# Booster_PA_OUT.net
KiCad netlist of a schematic drawn in Altium Designer
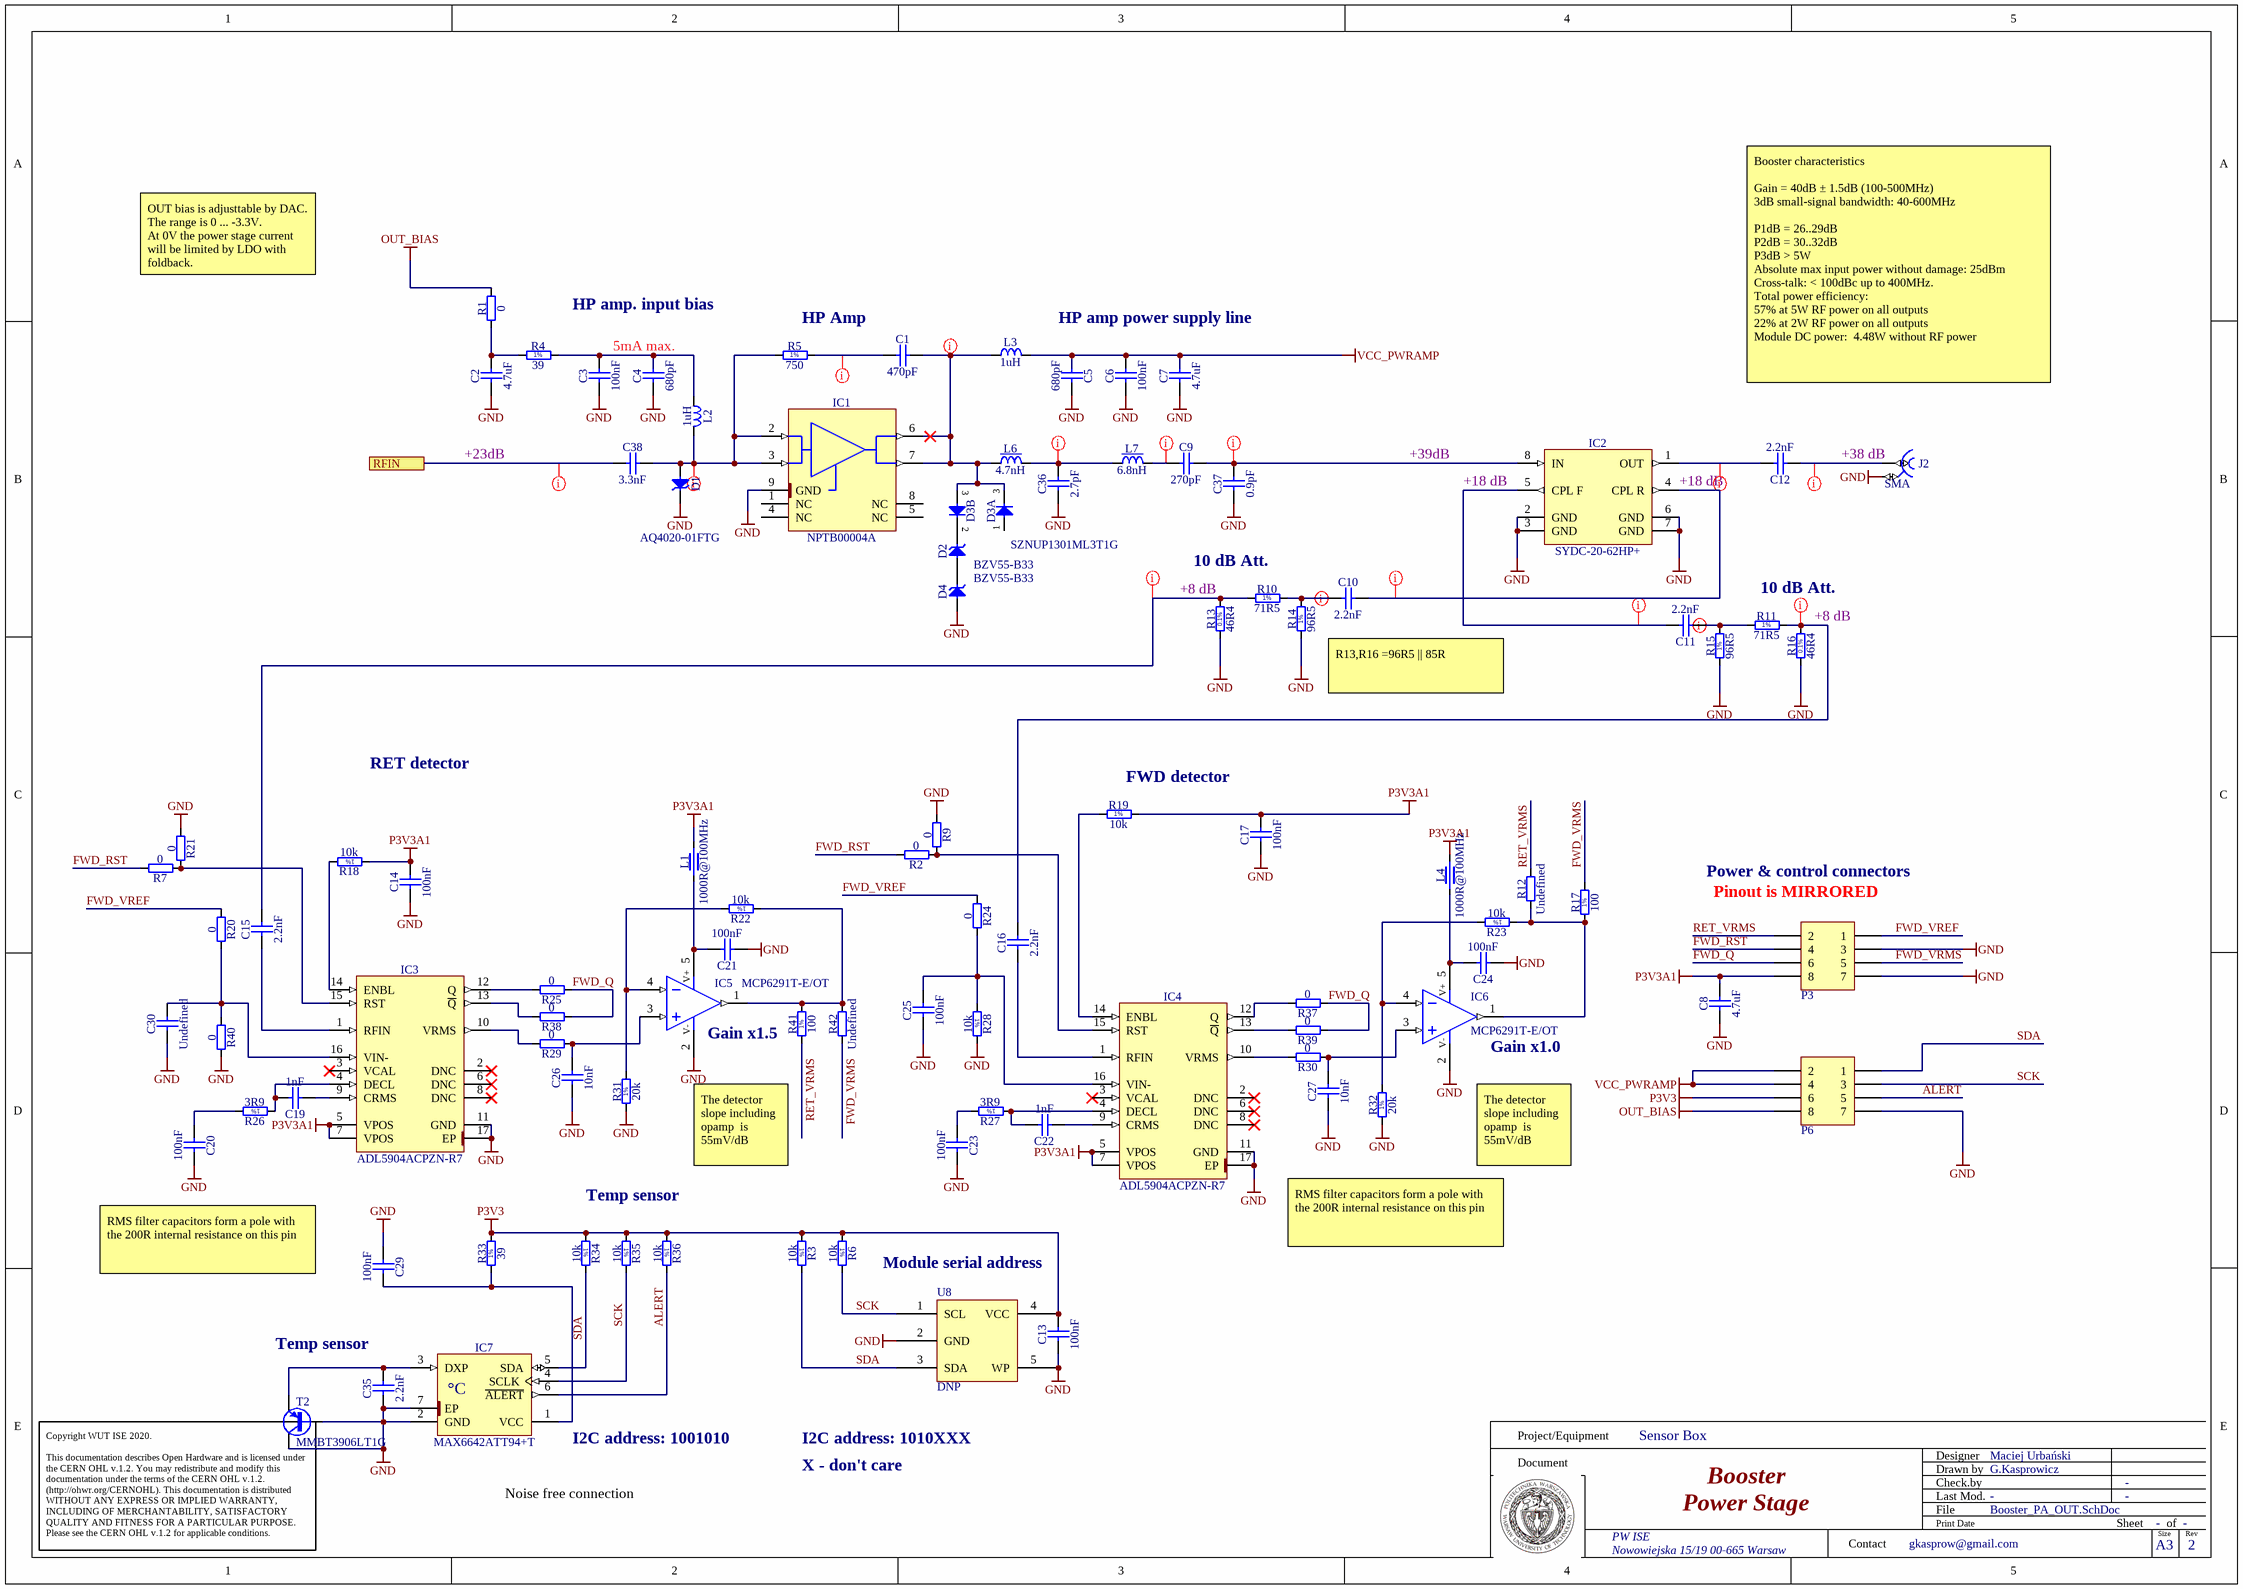
[diagram p0: Booster_PA_OUT.SchDoc]

(export (version "E")
  (design (tool "Eeschema 10.0.6"))
  (components
    (comp (ref "C1")
      (value "470pF")
      (footprint "CAPC1608X87N")
      (description "Non-polarised capacitor")
      (fields (field (name "PART NUMBER") "CC0603_470PF_50V_1%_NP0") (field (name "VOLTAGE") "50V"))
      (libsource (lib "Passives_RC") (part "CC0603_470PF_50V_1%_NP0"))
    )
    (comp (ref "C2")
      (value "4.7uF")
      (footprint "CAPC1709X95N")
      (description "Non-polarised capacitor")
      (fields
        (field (name "MANUFACTURER") "GENERIC")
        (field (name "MANUFACTURER PART NUMBER") "CC0603_4.7UF_16V_10%_X5R")
      )
      (libsource (lib "Capacitors") (part "Capacitor - non polarized"))
    )
    (comp (ref "C3")
      (value "100nF")
      (footprint "CAPC1005X55N")
      (description "Non-polarised capacitor")
      (fields
        (field (name "MANUFACTURER") "GENERIC")
        (field (name "MANUFACTURER PART NUMBER") "CC0402_100NF_50V_10%_X7R")
      )
      (libsource (lib "Capacitors") (part "Capacitor - non polarized"))
    )
    (comp (ref "C4")
      (value "680pF")
      (footprint "CAPC1608X87N")
      (description "Non-polarised capacitor")
      (fields
        (field (name "MANUFACTURER") "GENERIC")
        (field (name "MANUFACTURER PART NUMBER") "CC0603_680PF_50V_5%_NP0")
      )
      (libsource (lib "Capacitors") (part "Capacitor - non polarized"))
    )
    (comp (ref "C5")
      (value "680pF")
      (footprint "CAPC1608X87N")
      (description "Non-polarised capacitor")
      (fields
        (field (name "MANUFACTURER") "GENERIC")
        (field (name "MANUFACTURER PART NUMBER") "CC0603_680PF_50V_5%_NP0")
      )
      (libsource (lib "Capacitors") (part "Capacitor - non polarized"))
    )
    (comp (ref "C6")
      (value "100nF")
      (footprint "CAPC1005X55N")
      (description "Non-polarised capacitor")
      (fields
        (field (name "MANUFACTURER") "GENERIC")
        (field (name "MANUFACTURER PART NUMBER") "CC0402_100NF_50V_10%_X7R")
      )
      (libsource (lib "Capacitors") (part "Capacitor - non polarized"))
    )
    (comp (ref "C7")
      (value "4.7uF")
      (footprint "CAPC3225X270N")
      (description "Non-polarised capacitor")
      (fields (field (name "PART NUMBER") "CC1210_4.7UF_50V_10%_X7R") (field (name "VOLTAGE") "50V"))
      (libsource (lib "Capacitors") (part "Capacitor - non polarized"))
    )
    (comp (ref "C8")
      (value "4.7uF")
      (footprint "CAPC1709X95N")
      (description "Non-polarised capacitor")
      (fields
        (field (name "MANUFACTURER") "GENERIC")
        (field (name "MANUFACTURER PART NUMBER") "CC0603_4.7UF_16V_10%_X5R")
      )
      (libsource (lib "Capacitors") (part "Capacitor - non polarized"))
    )
    (comp (ref "C9")
      (value "270pF")
      (footprint "CAPC1608X87N")
      (description "Non-polarised capacitor")
      (fields (field (name "PART NUMBER") "CC0603_270PF_50V_1%_NP0") (field (name "VOLTAGE") "50V"))
      (libsource (lib "Passives_RC") (part "CC0603_270PF_50V_1%_NP0"))
    )
    (comp (ref "C10")
      (value "2.2nF")
      (footprint "CAPC1608X87N")
      (description "Non-polarised capacitor")
      (fields (field (name "PART NUMBER") "CC0603_2.2NF_50V_5%_C0G") (field (name "VOLTAGE") "50V"))
      (libsource (lib "Capacitors") (part "Capacitor - non polarized"))
    )
    (comp (ref "C11")
      (value "2.2nF")
      (footprint "CAPC1608X87N")
      (description "Non-polarised capacitor")
      (fields
        (field (name "MANUFACTURER") "GENERIC")
        (field (name "MANUFACTURER PART NUMBER") "CC0603_2.2NF_50V_5%_C0G")
      )
      (libsource (lib "Capacitors") (part "Capacitor - non polarized"))
    )
    (comp (ref "C12")
      (value "2.2nF")
      (footprint "CAPC1608X87N")
      (description "Non-polarised capacitor")
      (fields
        (field (name "MANUFACTURER") "GENERIC")
        (field (name "MANUFACTURER PART NUMBER") "CC0603_2.2NF_50V_5%_C0G")
      )
      (libsource (lib "Capacitors") (part "Capacitor - non polarized"))
    )
    (comp (ref "C13")
      (value "100nF")
      (footprint "CAPC1005X55N")
      (description "Non-polarised capacitor")
      (fields
        (field (name "MANUFACTURER") "GENERIC")
        (field (name "MANUFACTURER PART NUMBER") "CC0402_100NF_50V_10%_X7R")
      )
      (libsource (lib "Capacitors") (part "Capacitor - non polarized"))
    )
    (comp (ref "C14")
      (value "100nF")
      (footprint "CAPC1005X55N")
      (description "Non-polarised capacitor")
      (fields
        (field (name "MANUFACTURER") "GENERIC")
        (field (name "MANUFACTURER PART NUMBER") "CC0402_100NF_50V_10%_X7R")
      )
      (libsource (lib "Capacitors") (part "Capacitor - non polarized"))
    )
    (comp (ref "C15")
      (value "2.2nF")
      (footprint "CAPC1608X87N")
      (description "Non-polarised capacitor")
      (fields
        (field (name "MANUFACTURER") "GENERIC")
        (field (name "MANUFACTURER PART NUMBER") "CC0603_2.2NF_50V_5%_C0G")
      )
      (libsource (lib "Capacitors") (part "Capacitor - non polarized"))
    )
    (comp (ref "C16")
      (value "2.2nF")
      (footprint "CAPC1608X87N")
      (description "Non-polarised capacitor")
      (fields
        (field (name "MANUFACTURER") "GENERIC")
        (field (name "MANUFACTURER PART NUMBER") "CC0603_2.2NF_50V_5%_C0G")
      )
      (libsource (lib "Capacitors") (part "Capacitor - non polarized"))
    )
    (comp (ref "C17")
      (value "100nF")
      (footprint "CAPC1005X55N")
      (description "Non-polarised capacitor")
      (fields
        (field (name "MANUFACTURER") "GENERIC")
        (field (name "MANUFACTURER PART NUMBER") "CC0402_100NF_50V_10%_X7R")
      )
      (libsource (lib "Capacitors") (part "Capacitor - non polarized"))
    )
    (comp (ref "C19")
      (value "1nF")
      (footprint "CAPC1005X55N")
      (description "Non-polarised capacitor")
      (fields (field (name "PART NUMBER") "CC0402_1NF_50V_10%_X7R") (field (name "VOLTAGE") "50V"))
      (libsource (lib "Capacitors") (part "Capacitor - non polarized"))
    )
    (comp (ref "C20")
      (value "100nF")
      (footprint "CAPC1005X55N")
      (description "Non-polarised capacitor")
      (fields
        (field (name "MANUFACTURER") "GENERIC")
        (field (name "MANUFACTURER PART NUMBER") "CC0402_100NF_50V_10%_X7R")
      )
      (libsource (lib "Capacitors") (part "Capacitor - non polarized"))
    )
    (comp (ref "C21")
      (value "100nF")
      (footprint "CAPC1005X55N")
      (description "Non-polarised capacitor")
      (fields
        (field (name "MANUFACTURER") "GENERIC")
        (field (name "MANUFACTURER PART NUMBER") "CC0402_100NF_50V_10%_X7R")
      )
      (libsource (lib "Capacitors") (part "Capacitor - non polarized"))
    )
    (comp (ref "C22")
      (value "1nF")
      (footprint "CAPC1005X55N")
      (description "Non-polarised capacitor")
      (fields (field (name "PART NUMBER") "CC0402_1NF_50V_10%_X7R") (field (name "VOLTAGE") "50V"))
      (libsource (lib "Capacitors") (part "Capacitor - non polarized"))
    )
    (comp (ref "C23")
      (value "100nF")
      (footprint "CAPC1005X55N")
      (description "Non-polarised capacitor")
      (fields
        (field (name "MANUFACTURER") "GENERIC")
        (field (name "MANUFACTURER PART NUMBER") "CC0402_100NF_50V_10%_X7R")
      )
      (libsource (lib "Capacitors") (part "Capacitor - non polarized"))
    )
    (comp (ref "C24")
      (value "100nF")
      (footprint "CAPC1005X55N")
      (description "Non-polarised capacitor")
      (fields
        (field (name "MANUFACTURER") "GENERIC")
        (field (name "MANUFACTURER PART NUMBER") "CC0402_100NF_50V_10%_X7R")
      )
      (libsource (lib "Capacitors") (part "Capacitor - non polarized"))
    )
    (comp (ref "C25")
      (value "100nF")
      (footprint "CAPC1005X55N")
      (description "Non-polarised capacitor")
      (fields
        (field (name "MANUFACTURER") "GENERIC")
        (field (name "MANUFACTURER PART NUMBER") "CC0402_100NF_50V_10%_X7R")
      )
      (libsource (lib "Capacitors") (part "Capacitor - non polarized"))
    )
    (comp (ref "C26")
      (value "10nF")
      (footprint "CAPC1005X55N")
      (description "Non-polarised capacitor")
      (fields
        (field (name "MANUFACTURER") "GENERIC")
        (field (name "MANUFACTURER PART NUMBER") "CC0402_10NF_25V_10%_X7R")
      )
      (libsource (lib "Capacitors") (part "Capacitor - non polarized"))
    )
    (comp (ref "C27")
      (value "10nF")
      (footprint "CAPC1005X55N")
      (description "Non-polarised capacitor")
      (fields
        (field (name "MANUFACTURER") "GENERIC")
        (field (name "MANUFACTURER PART NUMBER") "CC0402_10NF_25V_10%_X7R")
      )
      (libsource (lib "Capacitors") (part "Capacitor - non polarized"))
    )
    (comp (ref "C29")
      (value "100nF")
      (footprint "CAPC1005X55N")
      (description "Non-polarised capacitor")
      (fields
        (field (name "MANUFACTURER") "GENERIC")
        (field (name "MANUFACTURER PART NUMBER") "CC0402_100NF_50V_10%_X7R")
      )
      (libsource (lib "Capacitors") (part "Capacitor - non polarized"))
    )
    (comp (ref "C30")
      (value "Undefined")
      (footprint "CAPC1608X90N")
      (description "Non-polarised capacitor")
      (fields (field (name "PART NUMBER") "CC0603_NO-VALUE"))
      (libsource (lib "Capacitors") (part "Capacitor - non polarized"))
    )
    (comp (ref "C35")
      (value "2.2nF")
      (footprint "CAPC1608X87N")
      (description "Non-polarised capacitor")
      (fields
        (field (name "MANUFACTURER") "GENERIC")
        (field (name "MANUFACTURER PART NUMBER") "CC0603_2.2NF_50V_5%_C0G")
      )
      (libsource (lib "Capacitors") (part "Capacitor - non polarized"))
    )
    (comp (ref "C36")
      (value "2.7pF")
      (footprint "CAPC1608X87N")
      (description "Non-polarised capacitor")
      (fields (field (name "PART NUMBER") "CC0603_2.7PF_50V_0.25PF_NP0") (field (name "VOLTAGE") "50V"))
      (libsource (lib "Capacitors") (part "Capacitor - non polarized"))
    )
    (comp (ref "C37")
      (value "0.9pF")
      (footprint "CAPC1608X87N")
      (description "Non-polarised capacitor")
      (fields (field (name "PART NUMBER") "CC0603_0.9PF_50V_0.05PF_NP0") (field (name "VOLTAGE") "50V"))
      (libsource (lib "Passives_RC") (part "CC0603_0.9PF_50V_0.05PF_NP0"))
    )
    (comp (ref "C38")
      (value "3.3nF")
      (footprint "CAPC1608X87N")
      (description "Non-polarised capacitor")
      (fields
        (field (name "MANUFACTURER") "GENERIC")
        (field (name "MANUFACTURER PART NUMBER") "CC0603_3.3NF_50V_5%_C0G")
      )
      (libsource (lib "Capacitors") (part "Capacitor - non polarized"))
    )
    (comp (ref "D1")
      (value "AQ4020-01FTG")
      (footprint "SOD2512X110N")
      (description "4V Transient Voltage Suppressor Diode (Uni-Directional)")
      (fields (field (name "VOLTAGE") "4V") (field (name "POWER") "735W"))
      (libsource (lib "Diodes") (part "D_TVS_AQ4020-01FTG"))
    )
    (comp (ref "D2")
      (value "BZV55-B33")
      (footprint "DIOMELF3515N")
      (description "Zener Diode")
      (fields (field (name "VOLTAGE") "33V") (field (name "POWER") "500mW"))
      (libsource (lib "ICs And Semiconductors") (part "Diode Zener"))
    )
    (comp (ref "D3")
      (value "SZNUP1301ML3T1G")
      (footprint "SOT95P240X110-3N")
      (description "Low Capacitance Diode Array for ESD Protection in a Single Data Line")
      (fields (field (name "VOLTAGE") "70V") (field (name "POWER") "215mA"))
      (libsource (lib "Diodes") (part "D_TVS_SZNUP1301ML3T1G"))
    )
    (comp (ref "D4")
      (value "BZV55-B33")
      (footprint "DIOMELF3515N")
      (description "Zener Diode")
      (fields (field (name "VOLTAGE") "33V") (field (name "POWER") "500mW"))
      (libsource (lib "ICs And Semiconductors") (part "Diode Zener"))
    )
    (comp (ref "IC1")
      (value "NPTB00004A")
      (footprint "SOIC127P610X167-9N-R245X335")
      (description "GaN Wideband Transistor 28V, 5W, DC - 6GHz")
      (fields (field (name "MANUFACTURER") "MACOM"))
      (libsource (lib "ICs And Semiconductors") (part "NPTB00004A"))
    )
    (comp (ref "IC2")
      (value "SYDC-20-62HP+")
      (footprint "MINI-CIRCUITS_AH202-1")
      (description "50Ohm, 10 to 540MHz, 25W, 20dB Bi-Directional Coupler")
      (fields (field (name "MANUFACTURER") "MINI-CIRCUITS"))
      (libsource (lib "ICs And Semiconductors") (part "SYDC-20-62HP+"))
    )
    (comp (ref "IC3")
      (value "ADL5904ACPZN-R7")
      (footprint "QFN50P300X300X80-17N-S175")
      (description "DC to 6 GHz, 45 dB TruPwr Detector With Envelope Threshold Detection")
      (fields (field (name "MANUFACTURER") "ANALOG DEVICES"))
      (libsource (lib "ICs And Semiconductors") (part "ADL5904"))
    )
    (comp (ref "IC4")
      (value "ADL5904ACPZN-R7")
      (footprint "QFN50P300X300X80-17N-S175")
      (description "DC to 6 GHz, 45 dB TruPwr Detector With Envelope Threshold Detection")
      (fields (field (name "MANUFACTURER") "ANALOG DEVICES"))
      (libsource (lib "ICs And Semiconductors") (part "ADL5904"))
    )
    (comp (ref "IC5")
      (value "MCP6291T-E/OT")
      (footprint "SOT95P270X145-5N")
      (description "Operational Amplifier")
      (fields (field (name "MANUFACTURER") "MICROCHIP TECHNOLOGY"))
      (libsource (lib "ICs And Semiconductors") (part "Operational Amplifier Type7"))
    )
    (comp (ref "IC6")
      (value "MCP6291T-E/OT")
      (footprint "SOT95P270X145-5N")
      (description "Operational Amplifier")
      (fields (field (name "MANUFACTURER") "MICROCHIP TECHNOLOGY"))
      (libsource (lib "ICs And Semiconductors") (part "Operational Amplifier Type7"))
    )
    (comp (ref "IC7")
      (value "MAX6642ATT94+T")
      (footprint "SON95P300X300X80-7N-R160X240")
      (description "±1°C, SMBus-Compatible Remote/Local Temperature Sensor with Overtemperature Alarm")
      (fields (field (name "MANUFACTURER") "MAXIM"))
      (libsource (lib "ICs And Semiconductors") (part "MAX6642ATT"))
    )
    (comp (ref "J2")
      (value "SMA")
      (footprint "MOLEX_73251-2120")
      (description "50 Ohm, SMA Edge Mount PCB, With Jam Nut And Lock Washer")
      (fields (field (name "PART NUMBER") "MOLEX_73251-2120") (field (name "MANUFACTURER") "MOLEX"))
      (libsource (lib "Connectors") (part "CON_SMA_RA_SMD_73251-2120"))
    )
    (comp (ref "L1")
      (value "1000R@100MHz")
      (footprint "INDC1608X95N")
      (fields
        (field (name "MANUFACTURER") "MURATA")
        (field (name "MANUFACTURER PART NUMBER") "BLM18HE102SN1")
        (field (name "PART NUMBER") "IND0603_MURATA_BLM18HE102SN1")
      )
      (libsource (lib "Inductors & Transformers") (part "Ferrite Bead"))
    )
    (comp (ref "L2")
      (value "1uH")
      (footprint "INDC2113X60N")
      (description "Inductor")
      (fields (field (name "PART NUMBER") "IND0805_1UH_20%_WURTH_74479773210") (field (name "POWER") "800mA"))
      (libsource (lib "Inductors & Transformers") (part "Inductor"))
    )
    (comp (ref "L3")
      (value "1uH")
      (footprint "INDC2113X60N")
      (description "Inductor")
      (fields (field (name "PART NUMBER") "IND0805_1UH_20%_WURTH_74479773210") (field (name "POWER") "800mA"))
      (libsource (lib "") (part "Inductor_1"))
    )
    (comp (ref "L4")
      (value "1000R@100MHz")
      (footprint "INDC1608X95N")
      (fields
        (field (name "MANUFACTURER") "MURATA")
        (field (name "MANUFACTURER PART NUMBER") "BLM18HE102SN1")
        (field (name "PART NUMBER") "IND0603_MURATA_BLM18HE102SN1")
      )
      (libsource (lib "Inductors & Transformers") (part "Ferrite Bead"))
    )
    (comp (ref "L6")
      (value "4.7nH")
      (footprint "IND_MURATA_LQW18AN_G8")
      (description "Inductor With Core")
      (fields
        (field (name "PART NUMBER") "IND0603_4.7NH_2%_MURATA_LQW18AN4N7G8Z")
        (field (name "POWER") "1.5A")
      )
      (libsource (lib "Inductors & Transformers") (part "Inductor With Magnetic core"))
    )
    (comp (ref "L7")
      (value "6.8nH")
      (footprint "IND_MURATA_LQW18AN_G8")
      (description "Inductor With Core")
      (fields
        (field (name "PART NUMBER") "IND0603_6.8NH_2%_MURATA_LQW18AN6N8G8Z")
        (field (name "POWER") "1.9A")
      )
      (libsource (lib "Inductors & Transformers") (part "Inductor With Magnetic core"))
    )
    (comp (ref "P3")
      (value "ZL264-8DG")
      (footprint "HDR2X4_SMD")
      (description "Header, 4-Pin, Dual Row")
      (libsource (lib "onyks") (part "HDR2X4"))
    )
    (comp (ref "P6")
      (value "ZL264-8DG")
      (footprint "HDR2X4_SMD")
      (description "Header, 4-Pin, Dual Row")
      (libsource (lib "onyks") (part "HDR2X4"))
    )
    (comp (ref "R1")
      (value "0")
      (footprint "RESC1005X40N")
      (description "Resistor")
      (fields
        (field (name "MANUFACTURER") "GENERIC")
        (field (name "MANUFACTURER PART NUMBER") "R0402_0R_JUMPER")
      )
      (libsource (lib "Resistors") (part "Resistor"))
    )
    (comp (ref "R2")
      (value "0")
      (footprint "RESC1005X40N")
      (description "Resistor")
      (fields
        (field (name "MANUFACTURER") "GENERIC")
        (field (name "MANUFACTURER PART NUMBER") "R0402_0R_JUMPER")
      )
      (libsource (lib "Resistors") (part "Resistor"))
    )
    (comp (ref "R3")
      (value "10k")
      (footprint "RESC1005X40N")
      (description "Resistor - 1%")
      (fields
        (field (name "MANUFACTURER") "GENERIC")
        (field (name "MANUFACTURER PART NUMBER") "R0402_10K_1%_0.0625W_100PPM")
      )
      (libsource (lib "Resistors") (part "Resistor - 1%"))
    )
    (comp (ref "R4")
      (value "39")
      (footprint "RESC1608X55N")
      (description "Resistor - 1%")
      (fields (field (name "PART NUMBER") "R0603_39R_1%_0.1W_100PPM") (field (name "POWER") "0.1W"))
      (libsource (lib "Resistors") (part "Resistor - 1%"))
    )
    (comp (ref "R5")
      (value "750")
      (footprint "RESC1608X55N")
      (description "Resistor - 1%")
      (fields (field (name "PART NUMBER") "R0603_750R_1%_0.1W_100PPM") (field (name "POWER") "0.1W"))
      (libsource (lib "Resistors") (part "Resistor - 1%"))
    )
    (comp (ref "R6")
      (value "10k")
      (footprint "RESC1005X40N")
      (description "Resistor - 1%")
      (fields
        (field (name "MANUFACTURER") "GENERIC")
        (field (name "MANUFACTURER PART NUMBER") "R0402_10K_1%_0.0625W_100PPM")
      )
      (libsource (lib "Resistors") (part "Resistor - 1%"))
    )
    (comp (ref "R7")
      (value "0")
      (footprint "RESC1005X40N")
      (description "Resistor")
      (fields
        (field (name "MANUFACTURER") "GENERIC")
        (field (name "MANUFACTURER PART NUMBER") "R0402_0R_JUMPER")
      )
      (libsource (lib "Resistors") (part "Resistor"))
    )
    (comp (ref "R9")
      (value "0")
      (footprint "RESC1005X40N")
      (description "Resistor")
      (fields
        (field (name "MANUFACTURER") "GENERIC")
        (field (name "MANUFACTURER PART NUMBER") "R0402_0R_JUMPER")
      )
      (libsource (lib "Resistors") (part "Resistor"))
    )
    (comp (ref "R10")
      (value "71R5")
      (footprint "RESC1608X55N")
      (description "Resistor - 1%")
      (fields (field (name "PART NUMBER") "R0603_71R5_1%_0.1W_100PPM") (field (name "POWER") "0.1W"))
      (libsource (lib "Resistors") (part "Resistor - 1%"))
    )
    (comp (ref "R11")
      (value "71R5")
      (footprint "RESC1608X55N")
      (description "Resistor - 1%")
      (fields (field (name "PART NUMBER") "R0603_71R5_1%_0.1W_100PPM") (field (name "POWER") "0.1W"))
      (libsource (lib "Resistors") (part "Resistor - 1%"))
    )
    (comp (ref "R12")
      (value "Undefined")
      (footprint "RESC1608X55N")
      (description "Resistor")
      (fields (field (name "MANUFACTURER PART NUMBER") "R0603_NO-VALUE"))
      (libsource (lib "Resistors") (part "Resistor"))
    )
    (comp (ref "R13")
      (value "46R4")
      (footprint "RESC1608X55N")
      (description "Resistor - 0.1%")
      (fields (field (name "PART NUMBER") "R0603_46R4_0.1%_0.063W_10PPM") (field (name "POWER") "0.063W"))
      (libsource (lib "Resistors") (part "Resistor - 0.1%"))
    )
    (comp (ref "R14")
      (value "96R5")
      (footprint "RESC1608X55N")
      (description "Resistor - 0.5%")
      (fields (field (name "PART NUMBER") "R0603_96R5_0.5%_0.1W_50PPM") (field (name "POWER") "0.1W"))
      (libsource (lib "Passives_RC") (part "R0603_96R5_0.5%_0.1W_50PPM"))
    )
    (comp (ref "R15")
      (value "96R5")
      (footprint "RESC1608X55N")
      (description "Resistor - 0.5%")
      (fields (field (name "PART NUMBER") "R0603_96R5_0.5%_0.1W_50PPM") (field (name "POWER") "0.1W"))
      (libsource (lib "Passives_RC") (part "R0603_96R5_0.5%_0.1W_50PPM"))
    )
    (comp (ref "R16")
      (value "46R4")
      (footprint "RESC1608X55N")
      (description "Resistor - 0.1%")
      (fields (field (name "PART NUMBER") "R0603_46R4_0.1%_0.063W_10PPM") (field (name "POWER") "0.063W"))
      (libsource (lib "Resistors") (part "Resistor - 0.1%"))
    )
    (comp (ref "R17")
      (value "100")
      (footprint "RESC1608X55N")
      (description "Resistor - 1%")
      (fields
        (field (name "MANUFACTURER") "GENERIC")
        (field (name "MANUFACTURER PART NUMBER") "R0603_100R_1%_0.1W_100PPM")
      )
      (libsource (lib "Resistors") (part "Resistor - 1%"))
    )
    (comp (ref "R18")
      (value "10k")
      (footprint "RESC1005X40N")
      (description "Resistor - 1%")
      (fields
        (field (name "MANUFACTURER") "GENERIC")
        (field (name "MANUFACTURER PART NUMBER") "R0402_10K_1%_0.0625W_100PPM")
      )
      (libsource (lib "Resistors") (part "Resistor - 1%"))
    )
    (comp (ref "R19")
      (value "10k")
      (footprint "RESC1005X40N")
      (description "Resistor - 1%")
      (fields (field (name "PART NUMBER") "R0402_10K_1%_0.0625W_100PPM") (field (name "POWER") "0.0625W"))
      (libsource (lib "Resistors") (part "Resistor - 1%"))
    )
    (comp (ref "R20")
      (value "0")
      (footprint "RESC1005X40N")
      (description "Resistor")
      (fields
        (field (name "MANUFACTURER") "GENERIC")
        (field (name "MANUFACTURER PART NUMBER") "R0402_0R_JUMPER")
      )
      (libsource (lib "Resistors") (part "Resistor"))
    )
    (comp (ref "R21")
      (value "0")
      (footprint "RESC1005X40N")
      (description "Resistor")
      (fields
        (field (name "MANUFACTURER") "GENERIC")
        (field (name "MANUFACTURER PART NUMBER") "R0402_0R_JUMPER")
      )
      (libsource (lib "Resistors") (part "Resistor"))
    )
    (comp (ref "R22")
      (value "10k")
      (footprint "RESC1005X40N")
      (description "Resistor - 1%")
      (fields
        (field (name "MANUFACTURER") "GENERIC")
        (field (name "MANUFACTURER PART NUMBER") "R0402_10K_1%_0.0625W_100PPM")
      )
      (libsource (lib "Resistors") (part "Resistor - 1%"))
    )
    (comp (ref "R23")
      (value "10k")
      (footprint "RESC1005X40N")
      (description "Resistor - 1%")
      (fields
        (field (name "MANUFACTURER") "GENERIC")
        (field (name "MANUFACTURER PART NUMBER") "R0402_10K_1%_0.0625W_100PPM")
      )
      (libsource (lib "Resistors") (part "Resistor - 1%"))
    )
    (comp (ref "R24")
      (value "0")
      (footprint "RESC1005X40N")
      (description "Resistor")
      (fields
        (field (name "MANUFACTURER") "GENERIC")
        (field (name "MANUFACTURER PART NUMBER") "R0402_0R_JUMPER")
      )
      (libsource (lib "Resistors") (part "Resistor"))
    )
    (comp (ref "R25")
      (value "0")
      (footprint "RESC1005X40N")
      (description "Resistor")
      (fields
        (field (name "MANUFACTURER") "GENERIC")
        (field (name "MANUFACTURER PART NUMBER") "R0402_0R_JUMPER")
      )
      (libsource (lib "Resistors") (part "Resistor"))
    )
    (comp (ref "R26")
      (value "3R9")
      (footprint "RESC1005X40N")
      (description "Resistor - 1%")
      (fields (field (name "PART NUMBER") "R0402_3R9_1%_0.0625W_200PPM") (field (name "POWER") "0.0625W"))
      (libsource (lib "Resistors") (part "Resistor - 1%"))
    )
    (comp (ref "R27")
      (value "3R9")
      (footprint "RESC1005X40N")
      (description "Resistor - 1%")
      (fields (field (name "PART NUMBER") "R0402_3R9_1%_0.0625W_200PPM") (field (name "POWER") "0.0625W"))
      (libsource (lib "Resistors") (part "Resistor - 1%"))
    )
    (comp (ref "R28")
      (value "10k")
      (footprint "RESC1005X40N")
      (description "Resistor - 1%")
      (fields
        (field (name "MANUFACTURER") "GENERIC")
        (field (name "MANUFACTURER PART NUMBER") "R0402_10K_1%_0.0625W_100PPM")
      )
      (libsource (lib "Resistors") (part "Resistor - 1%"))
    )
    (comp (ref "R29")
      (value "0")
      (footprint "RESC1005X40N")
      (description "Resistor")
      (fields
        (field (name "MANUFACTURER") "GENERIC")
        (field (name "MANUFACTURER PART NUMBER") "R0402_0R_JUMPER")
      )
      (libsource (lib "Resistors") (part "Resistor"))
    )
    (comp (ref "R30")
      (value "0")
      (footprint "RESC1005X40N")
      (description "Resistor")
      (fields
        (field (name "MANUFACTURER") "GENERIC")
        (field (name "MANUFACTURER PART NUMBER") "R0402_0R_JUMPER")
      )
      (libsource (lib "Resistors") (part "Resistor"))
    )
    (comp (ref "R31")
      (value "20k")
      (footprint "RESC1608X55N")
      (description "Resistor - 1%")
      (fields (field (name "PART NUMBER") "R0603_20K_1%_0.1W_100PPM") (field (name "POWER") "0.1W"))
      (libsource (lib "Resistors") (part "Resistor - 1%"))
    )
    (comp (ref "R32")
      (value "20k")
      (footprint "RESC1608X55N")
      (description "Resistor - 1%")
      (fields (field (name "PART NUMBER") "R0603_20K_1%_0.1W_100PPM") (field (name "POWER") "0.1W"))
      (libsource (lib "Resistors") (part "Resistor - 1%"))
    )
    (comp (ref "R33")
      (value "39")
      (footprint "RESC1608X55N")
      (description "Resistor - 1%")
      (fields (field (name "PART NUMBER") "R0603_39R_1%_0.1W_100PPM") (field (name "POWER") "0.1W"))
      (libsource (lib "Resistors") (part "Resistor - 1%"))
    )
    (comp (ref "R34")
      (value "10k")
      (footprint "RESC1005X40N")
      (description "Resistor - 1%")
      (fields
        (field (name "MANUFACTURER") "GENERIC")
        (field (name "MANUFACTURER PART NUMBER") "R0402_10K_1%_0.0625W_100PPM")
      )
      (libsource (lib "Resistors") (part "Resistor - 1%"))
    )
    (comp (ref "R35")
      (value "10k")
      (footprint "RESC1005X40N")
      (description "Resistor - 1%")
      (fields
        (field (name "MANUFACTURER") "GENERIC")
        (field (name "MANUFACTURER PART NUMBER") "R0402_10K_1%_0.0625W_100PPM")
      )
      (libsource (lib "Resistors") (part "Resistor - 1%"))
    )
    (comp (ref "R36")
      (value "10k")
      (footprint "RESC1005X40N")
      (description "Resistor - 1%")
      (fields
        (field (name "MANUFACTURER") "GENERIC")
        (field (name "MANUFACTURER PART NUMBER") "R0402_10K_1%_0.0625W_100PPM")
      )
      (libsource (lib "Resistors") (part "Resistor - 1%"))
    )
    (comp (ref "R37")
      (value "0")
      (footprint "RESC1005X40N")
      (description "Resistor")
      (fields
        (field (name "MANUFACTURER") "GENERIC")
        (field (name "MANUFACTURER PART NUMBER") "R0402_0R_JUMPER")
      )
      (libsource (lib "Resistors") (part "Resistor"))
    )
    (comp (ref "R38")
      (value "0")
      (footprint "RESC1005X40N")
      (description "Resistor")
      (fields
        (field (name "MANUFACTURER") "GENERIC")
        (field (name "MANUFACTURER PART NUMBER") "R0402_0R_JUMPER")
      )
      (libsource (lib "Resistors") (part "Resistor"))
    )
    (comp (ref "R39")
      (value "0")
      (footprint "RESC1005X40N")
      (description "Resistor")
      (fields
        (field (name "MANUFACTURER") "GENERIC")
        (field (name "MANUFACTURER PART NUMBER") "R0402_0R_JUMPER")
      )
      (libsource (lib "Resistors") (part "Resistor"))
    )
    (comp (ref "R40")
      (value "0")
      (footprint "RESC1005X40N")
      (description "Resistor")
      (fields
        (field (name "MANUFACTURER") "GENERIC")
        (field (name "MANUFACTURER PART NUMBER") "R0402_0R_JUMPER")
      )
      (libsource (lib "Resistors") (part "Resistor"))
    )
    (comp (ref "R41")
      (value "100")
      (footprint "RESC1608X55N")
      (description "Resistor - 1%")
      (fields
        (field (name "MANUFACTURER") "GENERIC")
        (field (name "MANUFACTURER PART NUMBER") "R0603_100R_1%_0.1W_100PPM")
      )
      (libsource (lib "Resistors") (part "Resistor - 1%"))
    )
    (comp (ref "R42")
      (value "Undefined")
      (footprint "RESC1608X55N")
      (description "Resistor")
      (fields (field (name "MANUFACTURER PART NUMBER") "R0603_NO-VALUE"))
      (libsource (lib "Resistors") (part "Resistor"))
    )
    (comp (ref "T2")
      (value "MMBT3906LT1G")
      (footprint "SOT95P240X110-3N")
      (description "PNP Transistor")
      (fields (field (name "MANUFACTURER") "ON SEMICONDUCTOR"))
      (libsource (lib "ICs And Semiconductors") (part "PNP B1 E2 C3"))
    )
    (comp (ref "U8")
      (value "DNP")
      (footprint "SOT23-5_N")
      (description "1K I2  C™ Serial EEPROM with Half-Array Write-Protect")
      (fields (field (name "MANUFACTURER") "Microchip"))
      (libsource (lib "uklady_cyfrowe") (part "24AA01H"))
    )
  )
  (nets
    (net (code "1") (name "/ALERT") (class "Default")
      (node (ref "IC7") (pin "6") (pinfunction "~{ALERT}_6") (pintype "output"))
      (node (ref "P6") (pin "5") (pinfunction "5_5") (pintype "passive"))
      (node (ref "R36") (pin "2") (pinfunction "2_2") (pintype "passive"))
    )
    (net (code "2") (name "/FWD_Q") (class "Default")
      (node (ref "P3") (pin "6") (pinfunction "6_6") (pintype "passive"))
      (node (ref "R25") (pin "1") (pinfunction "1_1") (pintype "passive"))
      (node (ref "R37") (pin "1") (pinfunction "1_1") (pintype "passive"))
      (node (ref "R38") (pin "1") (pinfunction "1_1") (pintype "passive"))
      (node (ref "R39") (pin "1") (pinfunction "1_1") (pintype "passive"))
    )
    (net (code "3") (name "/FWD_RST") (class "Default")
      (node (ref "P3") (pin "4") (pinfunction "4_4") (pintype "passive"))
      (node (ref "R2") (pin "2") (pinfunction "2_2") (pintype "passive"))
      (node (ref "R7") (pin "2") (pinfunction "2_2") (pintype "passive"))
    )
    (net (code "4") (name "/FWD_VREF") (class "Default")
      (node (ref "P3") (pin "1") (pinfunction "1_1") (pintype "passive"))
      (node (ref "R20") (pin "1") (pinfunction "1_1") (pintype "passive"))
      (node (ref "R24") (pin "1") (pinfunction "1_1") (pintype "passive"))
    )
    (net (code "5") (name "/FWD_VRMS") (class "Default")
      (node (ref "P3") (pin "5") (pinfunction "5_5") (pintype "passive"))
      (node (ref "R17") (pin "2") (pinfunction "2_2") (pintype "passive"))
      (node (ref "R42") (pin "1") (pinfunction "1_1") (pintype "passive"))
    )
    (net (code "6") (name "/RET_VRMS") (class "Default")
      (node (ref "P3") (pin "2") (pinfunction "2_2") (pintype "passive"))
      (node (ref "R12") (pin "2") (pinfunction "2_2") (pintype "passive"))
      (node (ref "R41") (pin "1") (pinfunction "1_1") (pintype "passive"))
    )
    (net (code "7") (name "/RFIN") (class "Default")
      (node (ref "C38") (pin "2") (pinfunction "2_2") (pintype "passive"))
    )
    (net (code "8") (name "/SCK") (class "Default")
      (node (ref "IC7") (pin "4") (pinfunction "SCLK_4") (pintype "input"))
      (node (ref "P6") (pin "3") (pinfunction "3_3") (pintype "passive"))
      (node (ref "R35") (pin "2") (pinfunction "2_2") (pintype "passive"))
      (node (ref "R6") (pin "2") (pinfunction "2_2") (pintype "passive"))
      (node (ref "U8") (pin "1") (pinfunction "SCL_1") (pintype "passive"))
    )
    (net (code "9") (name "/SDA") (class "Default")
      (node (ref "IC7") (pin "5") (pinfunction "SDA_5") (pintype "bidirectional"))
      (node (ref "P6") (pin "1") (pinfunction "1_1") (pintype "passive"))
      (node (ref "R3") (pin "2") (pinfunction "2_2") (pintype "passive"))
      (node (ref "R34") (pin "2") (pinfunction "2_2") (pintype "passive"))
      (node (ref "U8") (pin "3") (pinfunction "SDA_3") (pintype "passive"))
    )
    (net (code "10") (name "GND") (class "Default")
      (node (ref "C13") (pin "1") (pinfunction "1_1") (pintype "passive"))
      (node (ref "C14") (pin "1") (pinfunction "1_1") (pintype "passive"))
      (node (ref "C17") (pin "1") (pinfunction "1_1") (pintype "passive"))
      (node (ref "C2") (pin "1") (pinfunction "1_1") (pintype "passive"))
      (node (ref "C20") (pin "2") (pinfunction "2_2") (pintype "passive"))
      (node (ref "C21") (pin "1") (pinfunction "1_1") (pintype "passive"))
      (node (ref "C23") (pin "2") (pinfunction "2_2") (pintype "passive"))
      (node (ref "C24") (pin "1") (pinfunction "1_1") (pintype "passive"))
      (node (ref "C25") (pin "1") (pinfunction "1_1") (pintype "passive"))
      (node (ref "C26") (pin "1") (pinfunction "1_1") (pintype "passive"))
      (node (ref "C27") (pin "1") (pinfunction "1_1") (pintype "passive"))
      (node (ref "C29") (pin "1") (pinfunction "1_1") (pintype "passive"))
      (node (ref "C3") (pin "1") (pinfunction "1_1") (pintype "passive"))
      (node (ref "C30") (pin "1") (pinfunction "1_1") (pintype "passive"))
      (node (ref "C35") (pin "1") (pinfunction "1_1") (pintype "passive"))
      (node (ref "C36") (pin "1") (pinfunction "1_1") (pintype "passive"))
      (node (ref "C37") (pin "1") (pinfunction "1_1") (pintype "passive"))
      (node (ref "C4") (pin "1") (pinfunction "1_1") (pintype "passive"))
      (node (ref "C5") (pin "1") (pinfunction "1_1") (pintype "passive"))
      (node (ref "C6") (pin "1") (pinfunction "1_1") (pintype "passive"))
      (node (ref "C7") (pin "1") (pinfunction "1_1") (pintype "passive"))
      (node (ref "C8") (pin "1") (pinfunction "1_1") (pintype "passive"))
      (node (ref "D1") (pin "1") (pinfunction "C_1") (pintype "passive"))
      (node (ref "D4") (pin "2") (pinfunction "A_2") (pintype "passive"))
      (node (ref "IC1") (pin "9") (pinfunction "GND_9") (pintype "power_in"))
      (node (ref "IC2") (pin "2") (pinfunction "GND_2") (pintype "power_in"))
      (node (ref "IC2") (pin "3") (pinfunction "GND_3") (pintype "power_in"))
      (node (ref "IC2") (pin "6") (pinfunction "GND_6") (pintype "power_in"))
      (node (ref "IC2") (pin "7") (pinfunction "GND_7") (pintype "power_in"))
      (node (ref "IC3") (pin "11") (pinfunction "GND_11") (pintype "power_in"))
      (node (ref "IC3") (pin "17") (pinfunction "EP_17") (pintype "power_in"))
      (node (ref "IC4") (pin "11") (pinfunction "GND_11") (pintype "power_in"))
      (node (ref "IC4") (pin "17") (pinfunction "EP_17") (pintype "power_in"))
      (node (ref "IC5") (pin "2") (pinfunction "V-_2") (pintype "power_in"))
      (node (ref "IC6") (pin "2") (pinfunction "V-_2") (pintype "power_in"))
      (node (ref "IC7") (pin "2") (pinfunction "GND_2") (pintype "power_in"))
      (node (ref "IC7") (pin "7") (pinfunction "EP_7") (pintype "power_in"))
      (node (ref "J2") (pin "2") (pinfunction "2_2") (pintype "bidirectional"))
      (node (ref "P3") (pin "3") (pinfunction "3_3") (pintype "passive"))
      (node (ref "P3") (pin "7") (pinfunction "7_7") (pintype "passive"))
      (node (ref "P6") (pin "7") (pinfunction "7_7") (pintype "passive"))
      (node (ref "R13") (pin "1") (pinfunction "1_1") (pintype "passive"))
      (node (ref "R14") (pin "1") (pinfunction "1_1") (pintype "passive"))
      (node (ref "R15") (pin "1") (pinfunction "1_1") (pintype "passive"))
      (node (ref "R16") (pin "1") (pinfunction "1_1") (pintype "passive"))
      (node (ref "R21") (pin "1") (pinfunction "1_1") (pintype "passive"))
      (node (ref "R28") (pin "2") (pinfunction "2_2") (pintype "passive"))
      (node (ref "R31") (pin "1") (pinfunction "1_1") (pintype "passive"))
      (node (ref "R32") (pin "1") (pinfunction "1_1") (pintype "passive"))
      (node (ref "R40") (pin "2") (pinfunction "2_2") (pintype "passive"))
      (node (ref "R9") (pin "1") (pinfunction "1_1") (pintype "passive"))
      (node (ref "T2") (pin "1") (pinfunction "B_1") (pintype "passive"))
      (node (ref "T2") (pin "3") (pinfunction "C_3") (pintype "passive"))
      (node (ref "U8") (pin "2") (pinfunction "GND_2") (pintype "passive"))
      (node (ref "U8") (pin "5") (pinfunction "WP_5") (pintype "passive"))
    )
    (net (code "11") (name "Net-(C1-Pad1)") (class "Default")
      (node (ref "C1") (pin "1") (pinfunction "1_1") (pintype "passive"))
      (node (ref "R5") (pin "2") (pinfunction "2_2") (pintype "passive"))
    )
    (net (code "12") (name "Net-(C2-Pad2)") (class "Default")
      (node (ref "C2") (pin "2") (pinfunction "2_2") (pintype "passive"))
      (node (ref "R1") (pin "1") (pinfunction "1_1") (pintype "passive"))
      (node (ref "R4") (pin "1") (pinfunction "1_1") (pintype "passive"))
    )
    (net (code "13") (name "Net-(C3-Pad2)") (class "Default")
      (node (ref "C3") (pin "2") (pinfunction "2_2") (pintype "passive"))
      (node (ref "C4") (pin "2") (pinfunction "2_2") (pintype "passive"))
      (node (ref "L2") (pin "1") (pinfunction "1_1") (pintype "passive"))
      (node (ref "R4") (pin "2") (pinfunction "2_2") (pintype "passive"))
    )
    (net (code "14") (name "Net-(C9-Pad1)") (class "Default")
      (node (ref "C9") (pin "1") (pinfunction "1_1") (pintype "passive"))
      (node (ref "L7") (pin "2") (pinfunction "2_2") (pintype "passive"))
    )
    (net (code "15") (name "Net-(C10-Pad1)") (class "Default")
      (node (ref "C10") (pin "1") (pinfunction "1_1") (pintype "passive"))
      (node (ref "R10") (pin "2") (pinfunction "2_2") (pintype "passive"))
      (node (ref "R14") (pin "2") (pinfunction "2_2") (pintype "passive"))
    )
    (net (code "16") (name "Net-(C11-Pad1)") (class "Default")
      (node (ref "C11") (pin "1") (pinfunction "1_1") (pintype "passive"))
      (node (ref "R11") (pin "1") (pinfunction "1_1") (pintype "passive"))
      (node (ref "R15") (pin "2") (pinfunction "2_2") (pintype "passive"))
    )
    (net (code "17") (name "Net-(C12-Pad1)") (class "Default")
      (node (ref "C12") (pin "1") (pinfunction "1_1") (pintype "passive"))
      (node (ref "J2") (pin "1") (pinfunction "1_1") (pintype "bidirectional"))
    )
    (net (code "18") (name "Net-(C15-Pad2)") (class "Default")
      (node (ref "C15") (pin "2") (pinfunction "2_2") (pintype "passive"))
      (node (ref "R10") (pin "1") (pinfunction "1_1") (pintype "passive"))
      (node (ref "R13") (pin "2") (pinfunction "2_2") (pintype "passive"))
    )
    (net (code "19") (name "Net-(C16-Pad2)") (class "Default")
      (node (ref "C16") (pin "2") (pinfunction "2_2") (pintype "passive"))
      (node (ref "R11") (pin "2") (pinfunction "2_2") (pintype "passive"))
      (node (ref "R16") (pin "2") (pinfunction "2_2") (pintype "passive"))
    )
    (net (code "20") (name "Net-(C20-Pad1)") (class "Default")
      (node (ref "C20") (pin "1") (pinfunction "1_1") (pintype "passive"))
      (node (ref "R26") (pin "2") (pinfunction "2_2") (pintype "passive"))
    )
    (net (code "21") (name "Net-(C23-Pad1)") (class "Default")
      (node (ref "C23") (pin "1") (pinfunction "1_1") (pintype "passive"))
      (node (ref "R27") (pin "2") (pinfunction "2_2") (pintype "passive"))
    )
    (net (code "22") (name "Net-(C36-Pad2)") (class "Default")
      (node (ref "C36") (pin "2") (pinfunction "2_2") (pintype "passive"))
      (node (ref "L6") (pin "2") (pinfunction "2_2") (pintype "passive"))
      (node (ref "L7") (pin "1") (pinfunction "1_1") (pintype "passive"))
    )
    (net (code "23") (name "Net-(D1-A)") (class "Default")
      (node (ref "C38") (pin "1") (pinfunction "1_1") (pintype "passive"))
      (node (ref "D1") (pin "2") (pinfunction "A_2") (pintype "passive"))
      (node (ref "IC1") (pin "2") (pinfunction "RF_IN_2") (pintype "input"))
      (node (ref "IC1") (pin "3") (pinfunction "RF_IN_3") (pintype "input"))
      (node (ref "L2") (pin "2") (pinfunction "2_2") (pintype "passive"))
      (node (ref "R5") (pin "1") (pinfunction "1_1") (pintype "passive"))
    )
    (net (code "24") (name "Net-(D2-A)") (class "Default")
      (node (ref "D2") (pin "2") (pinfunction "A_2") (pintype "passive"))
      (node (ref "D4") (pin "1") (pinfunction "C_1") (pintype "passive"))
    )
    (net (code "25") (name "Net-(D2-C)") (class "Default")
      (node (ref "D2") (pin "1") (pinfunction "C_1") (pintype "passive"))
      (node (ref "D3") (pin "2") (pinfunction "C_2") (pintype "passive"))
    )
    (net (code "26") (name "Net-(D3A-COMAC)") (class "Default")
      (node (ref "C1") (pin "2") (pinfunction "2_2") (pintype "passive"))
      (node (ref "D3") (pin "3") (pinfunction "COMAC_3") (pintype "passive"))
      (node (ref "IC1") (pin "6") (pinfunction "RF_OUT_6") (pintype "output"))
      (node (ref "IC1") (pin "7") (pinfunction "RF_OUT_7") (pintype "output"))
      (node (ref "L3") (pin "1") (pinfunction "1_1") (pintype "passive"))
      (node (ref "L6") (pin "1") (pinfunction "1_1") (pintype "passive"))
    )
    (net (code "27") (name "Net-(IC2-CPL_F)") (class "Default")
      (node (ref "C11") (pin "2") (pinfunction "2_2") (pintype "passive"))
      (node (ref "IC2") (pin "5") (pinfunction "CPL_F_5") (pintype "output"))
    )
    (net (code "28") (name "Net-(IC2-CPL_R)") (class "Default")
      (node (ref "C10") (pin "2") (pinfunction "2_2") (pintype "passive"))
      (node (ref "IC2") (pin "4") (pinfunction "CPL_R_4") (pintype "output"))
    )
    (net (code "29") (name "Net-(IC2-IN)") (class "Default")
      (node (ref "C37") (pin "2") (pinfunction "2_2") (pintype "passive"))
      (node (ref "C9") (pin "2") (pinfunction "2_2") (pintype "passive"))
      (node (ref "IC2") (pin "8") (pinfunction "IN_8") (pintype "input"))
    )
    (net (code "30") (name "Net-(IC2-OUT)") (class "Default")
      (node (ref "C12") (pin "2") (pinfunction "2_2") (pintype "passive"))
      (node (ref "IC2") (pin "1") (pinfunction "OUT_1") (pintype "output"))
    )
    (net (code "31") (name "Net-(IC3-CRMS)") (class "Default")
      (node (ref "C19") (pin "1") (pinfunction "1_1") (pintype "passive"))
      (node (ref "IC3") (pin "9") (pinfunction "CRMS_9") (pintype "input"))
    )
    (net (code "32") (name "Net-(IC3-DECL)") (class "Default")
      (node (ref "C19") (pin "2") (pinfunction "2_2") (pintype "passive"))
      (node (ref "IC3") (pin "4") (pinfunction "DECL_4") (pintype "input"))
      (node (ref "R26") (pin "1") (pinfunction "1_1") (pintype "passive"))
    )
    (net (code "33") (name "Net-(IC3-ENBL)") (class "Default")
      (node (ref "IC3") (pin "14") (pinfunction "ENBL_14") (pintype "input"))
      (node (ref "R18") (pin "2") (pinfunction "2_2") (pintype "passive"))
    )
    (net (code "34") (name "Net-(IC3-Q)") (class "Default")
      (node (ref "IC3") (pin "12") (pinfunction "Q_12") (pintype "output"))
      (node (ref "R25") (pin "2") (pinfunction "2_2") (pintype "passive"))
    )
    (net (code "35") (name "Net-(IC3-RFIN)") (class "Default")
      (node (ref "C15") (pin "1") (pinfunction "1_1") (pintype "passive"))
      (node (ref "IC3") (pin "1") (pinfunction "RFIN_1") (pintype "input"))
    )
    (net (code "36") (name "Net-(IC3-RST)") (class "Default")
      (node (ref "IC3") (pin "15") (pinfunction "RST_15") (pintype "input"))
      (node (ref "R21") (pin "2") (pinfunction "2_2") (pintype "passive"))
      (node (ref "R7") (pin "1") (pinfunction "1_1") (pintype "passive"))
    )
    (net (code "37") (name "Net-(IC3-VIN-)") (class "Default")
      (node (ref "C30") (pin "2") (pinfunction "2_2") (pintype "passive"))
      (node (ref "IC3") (pin "16") (pinfunction "VIN-_16") (pintype "input"))
      (node (ref "R20") (pin "2") (pinfunction "2_2") (pintype "passive"))
      (node (ref "R40") (pin "1") (pinfunction "1_1") (pintype "passive"))
    )
    (net (code "38") (name "Net-(IC3-VRMS)") (class "Default")
      (node (ref "IC3") (pin "10") (pinfunction "VRMS_10") (pintype "output"))
      (node (ref "R29") (pin "2") (pinfunction "2_2") (pintype "passive"))
    )
    (net (code "39") (name "Net-(IC3-~{Q})") (class "Default")
      (node (ref "IC3") (pin "13") (pinfunction "~{Q}_13") (pintype "output"))
      (node (ref "R38") (pin "2") (pinfunction "2_2") (pintype "passive"))
    )
    (net (code "40") (name "Net-(IC4-CRMS)") (class "Default")
      (node (ref "C22") (pin "1") (pinfunction "1_1") (pintype "passive"))
      (node (ref "IC4") (pin "9") (pinfunction "CRMS_9") (pintype "input"))
    )
    (net (code "41") (name "Net-(IC4-DECL)") (class "Default")
      (node (ref "C22") (pin "2") (pinfunction "2_2") (pintype "passive"))
      (node (ref "IC4") (pin "4") (pinfunction "DECL_4") (pintype "input"))
      (node (ref "R27") (pin "1") (pinfunction "1_1") (pintype "passive"))
    )
    (net (code "42") (name "Net-(IC4-ENBL)") (class "Default")
      (node (ref "IC4") (pin "14") (pinfunction "ENBL_14") (pintype "input"))
      (node (ref "R19") (pin "1") (pinfunction "1_1") (pintype "passive"))
    )
    (net (code "43") (name "Net-(IC4-Q)") (class "Default")
      (node (ref "IC4") (pin "12") (pinfunction "Q_12") (pintype "output"))
      (node (ref "R37") (pin "2") (pinfunction "2_2") (pintype "passive"))
    )
    (net (code "44") (name "Net-(IC4-RFIN)") (class "Default")
      (node (ref "C16") (pin "1") (pinfunction "1_1") (pintype "passive"))
      (node (ref "IC4") (pin "1") (pinfunction "RFIN_1") (pintype "input"))
    )
    (net (code "45") (name "Net-(IC4-RST)") (class "Default")
      (node (ref "IC4") (pin "15") (pinfunction "RST_15") (pintype "input"))
      (node (ref "R2") (pin "1") (pinfunction "1_1") (pintype "passive"))
      (node (ref "R9") (pin "2") (pinfunction "2_2") (pintype "passive"))
    )
    (net (code "46") (name "Net-(IC4-VIN-)") (class "Default")
      (node (ref "C25") (pin "2") (pinfunction "2_2") (pintype "passive"))
      (node (ref "IC4") (pin "16") (pinfunction "VIN-_16") (pintype "input"))
      (node (ref "R24") (pin "2") (pinfunction "2_2") (pintype "passive"))
      (node (ref "R28") (pin "1") (pinfunction "1_1") (pintype "passive"))
    )
    (net (code "47") (name "Net-(IC4-VRMS)") (class "Default")
      (node (ref "IC4") (pin "10") (pinfunction "VRMS_10") (pintype "output"))
      (node (ref "R30") (pin "2") (pinfunction "2_2") (pintype "passive"))
    )
    (net (code "48") (name "Net-(IC4-~{Q})") (class "Default")
      (node (ref "IC4") (pin "13") (pinfunction "~{Q}_13") (pintype "output"))
      (node (ref "R39") (pin "2") (pinfunction "2_2") (pintype "passive"))
    )
    (net (code "49") (name "Net-(IC5-IN+)") (class "Default")
      (node (ref "C26") (pin "2") (pinfunction "2_2") (pintype "passive"))
      (node (ref "IC5") (pin "3") (pinfunction "IN+_3") (pintype "input"))
      (node (ref "R29") (pin "1") (pinfunction "1_1") (pintype "passive"))
    )
    (net (code "50") (name "Net-(IC5-IN-)") (class "Default")
      (node (ref "IC5") (pin "4") (pinfunction "IN-_4") (pintype "input"))
      (node (ref "R22") (pin "2") (pinfunction "2_2") (pintype "passive"))
      (node (ref "R31") (pin "2") (pinfunction "2_2") (pintype "passive"))
    )
    (net (code "51") (name "Net-(IC5-OUT)") (class "Default")
      (node (ref "IC5") (pin "1") (pinfunction "OUT_1") (pintype "output"))
      (node (ref "R22") (pin "1") (pinfunction "1_1") (pintype "passive"))
      (node (ref "R41") (pin "2") (pinfunction "2_2") (pintype "passive"))
      (node (ref "R42") (pin "2") (pinfunction "2_2") (pintype "passive"))
    )
    (net (code "52") (name "Net-(IC5-V+)") (class "Default")
      (node (ref "C21") (pin "2") (pinfunction "2_2") (pintype "passive"))
      (node (ref "IC5") (pin "5") (pinfunction "V+_5") (pintype "power_in"))
      (node (ref "L1") (pin "1") (pinfunction "1_1") (pintype "passive"))
    )
    (net (code "53") (name "Net-(IC6-IN+)") (class "Default")
      (node (ref "C27") (pin "2") (pinfunction "2_2") (pintype "passive"))
      (node (ref "IC6") (pin "3") (pinfunction "IN+_3") (pintype "input"))
      (node (ref "R30") (pin "1") (pinfunction "1_1") (pintype "passive"))
    )
    (net (code "54") (name "Net-(IC6-IN-)") (class "Default")
      (node (ref "IC6") (pin "4") (pinfunction "IN-_4") (pintype "input"))
      (node (ref "R23") (pin "2") (pinfunction "2_2") (pintype "passive"))
      (node (ref "R32") (pin "2") (pinfunction "2_2") (pintype "passive"))
    )
    (net (code "55") (name "Net-(IC6-OUT)") (class "Default")
      (node (ref "IC6") (pin "1") (pinfunction "OUT_1") (pintype "output"))
      (node (ref "R12") (pin "1") (pinfunction "1_1") (pintype "passive"))
      (node (ref "R17") (pin "1") (pinfunction "1_1") (pintype "passive"))
      (node (ref "R23") (pin "1") (pinfunction "1_1") (pintype "passive"))
    )
    (net (code "56") (name "Net-(IC6-V+)") (class "Default")
      (node (ref "C24") (pin "2") (pinfunction "2_2") (pintype "passive"))
      (node (ref "IC6") (pin "5") (pinfunction "V+_5") (pintype "power_in"))
      (node (ref "L4") (pin "1") (pinfunction "1_1") (pintype "passive"))
    )
    (net (code "57") (name "Net-(IC7-DXP)") (class "Default")
      (node (ref "C35") (pin "2") (pinfunction "2_2") (pintype "passive"))
      (node (ref "IC7") (pin "3") (pinfunction "DXP_3") (pintype "input"))
      (node (ref "T2") (pin "2") (pinfunction "E_2") (pintype "passive"))
    )
    (net (code "58") (name "Net-(IC7-VCC)") (class "Default")
      (node (ref "C29") (pin "2") (pinfunction "2_2") (pintype "passive"))
      (node (ref "IC7") (pin "1") (pinfunction "VCC_1") (pintype "power_in"))
      (node (ref "R33") (pin "1") (pinfunction "1_1") (pintype "passive"))
    )
    (net (code "59") (name "OUT_BIAS") (class "Default")
      (node (ref "P6") (pin "8") (pinfunction "8_8") (pintype "passive"))
      (node (ref "R1") (pin "2") (pinfunction "2_2") (pintype "passive"))
    )
    (net (code "60") (name "P3V3") (class "Default")
      (node (ref "C13") (pin "2") (pinfunction "2_2") (pintype "passive"))
      (node (ref "P6") (pin "6") (pinfunction "6_6") (pintype "passive"))
      (node (ref "R3") (pin "1") (pinfunction "1_1") (pintype "passive"))
      (node (ref "R33") (pin "2") (pinfunction "2_2") (pintype "passive"))
      (node (ref "R34") (pin "1") (pinfunction "1_1") (pintype "passive"))
      (node (ref "R35") (pin "1") (pinfunction "1_1") (pintype "passive"))
      (node (ref "R36") (pin "1") (pinfunction "1_1") (pintype "passive"))
      (node (ref "R6") (pin "1") (pinfunction "1_1") (pintype "passive"))
      (node (ref "U8") (pin "4") (pinfunction "VCC_4") (pintype "passive"))
    )
    (net (code "61") (name "P3V3A1") (class "Default")
      (node (ref "C14") (pin "2") (pinfunction "2_2") (pintype "passive"))
      (node (ref "C17") (pin "2") (pinfunction "2_2") (pintype "passive"))
      (node (ref "C8") (pin "2") (pinfunction "2_2") (pintype "passive"))
      (node (ref "IC3") (pin "5") (pinfunction "VPOS_5") (pintype "power_in"))
      (node (ref "IC3") (pin "7") (pinfunction "VPOS_7") (pintype "power_in"))
      (node (ref "IC4") (pin "5") (pinfunction "VPOS_5") (pintype "power_in"))
      (node (ref "IC4") (pin "7") (pinfunction "VPOS_7") (pintype "power_in"))
      (node (ref "L1") (pin "2") (pinfunction "2_2") (pintype "passive"))
      (node (ref "L4") (pin "2") (pinfunction "2_2") (pintype "passive"))
      (node (ref "P3") (pin "8") (pinfunction "8_8") (pintype "passive"))
      (node (ref "R18") (pin "1") (pinfunction "1_1") (pintype "passive"))
      (node (ref "R19") (pin "2") (pinfunction "2_2") (pintype "passive"))
    )
    (net (code "62") (name "VCC_PWRAMP") (class "Default")
      (node (ref "C5") (pin "2") (pinfunction "2_2") (pintype "passive"))
      (node (ref "C6") (pin "2") (pinfunction "2_2") (pintype "passive"))
      (node (ref "C7") (pin "2") (pinfunction "2_2") (pintype "passive"))
      (node (ref "L3") (pin "2") (pinfunction "2_2") (pintype "passive"))
      (node (ref "P6") (pin "2") (pinfunction "2_2") (pintype "passive"))
      (node (ref "P6") (pin "4") (pinfunction "4_4") (pintype "passive"))
    )
    (net (code "63") (name "unconnected-(D3A-A-Pad1)") (class "Default")
      (node (ref "D3") (pin "1") (pinfunction "A_1") (pintype "passive"))
    )
    (net (code "64") (name "unconnected-(IC1-NC-Pad1)") (class "Default")
      (node (ref "IC1") (pin "1") (pinfunction "NC_1") (pintype "passive"))
    )
    (net (code "65") (name "unconnected-(IC1-NC-Pad4)") (class "Default")
      (node (ref "IC1") (pin "4") (pinfunction "NC_4") (pintype "passive"))
    )
    (net (code "66") (name "unconnected-(IC1-NC-Pad5)") (class "Default")
      (node (ref "IC1") (pin "5") (pinfunction "NC_5") (pintype "power_in"))
    )
    (net (code "67") (name "unconnected-(IC1-NC-Pad8)") (class "Default")
      (node (ref "IC1") (pin "8") (pinfunction "NC_8") (pintype "power_in"))
    )
    (net (code "68") (name "unconnected-(IC3-DNC-Pad2)") (class "Default")
      (node (ref "IC3") (pin "2") (pinfunction "DNC_2") (pintype "passive+no_connect"))
    )
    (net (code "69") (name "unconnected-(IC3-DNC-Pad6)") (class "Default")
      (node (ref "IC3") (pin "6") (pinfunction "DNC_6") (pintype "passive+no_connect"))
    )
    (net (code "70") (name "unconnected-(IC3-DNC-Pad8)") (class "Default")
      (node (ref "IC3") (pin "8") (pinfunction "DNC_8") (pintype "passive+no_connect"))
    )
    (net (code "71") (name "unconnected-(IC3-VCAL-Pad3)") (class "Default")
      (node (ref "IC3") (pin "3") (pinfunction "VCAL_3") (pintype "input+no_connect"))
    )
    (net (code "72") (name "unconnected-(IC4-DNC-Pad2)") (class "Default")
      (node (ref "IC4") (pin "2") (pinfunction "DNC_2") (pintype "passive+no_connect"))
    )
    (net (code "73") (name "unconnected-(IC4-DNC-Pad6)") (class "Default")
      (node (ref "IC4") (pin "6") (pinfunction "DNC_6") (pintype "passive+no_connect"))
    )
    (net (code "74") (name "unconnected-(IC4-DNC-Pad8)") (class "Default")
      (node (ref "IC4") (pin "8") (pinfunction "DNC_8") (pintype "passive+no_connect"))
    )
    (net (code "75") (name "unconnected-(IC4-VCAL-Pad3)") (class "Default")
      (node (ref "IC4") (pin "3") (pinfunction "VCAL_3") (pintype "input+no_connect"))
    )
  )
)
